# taco.net
KiCad netlist of a schematic drawn in EAGLE
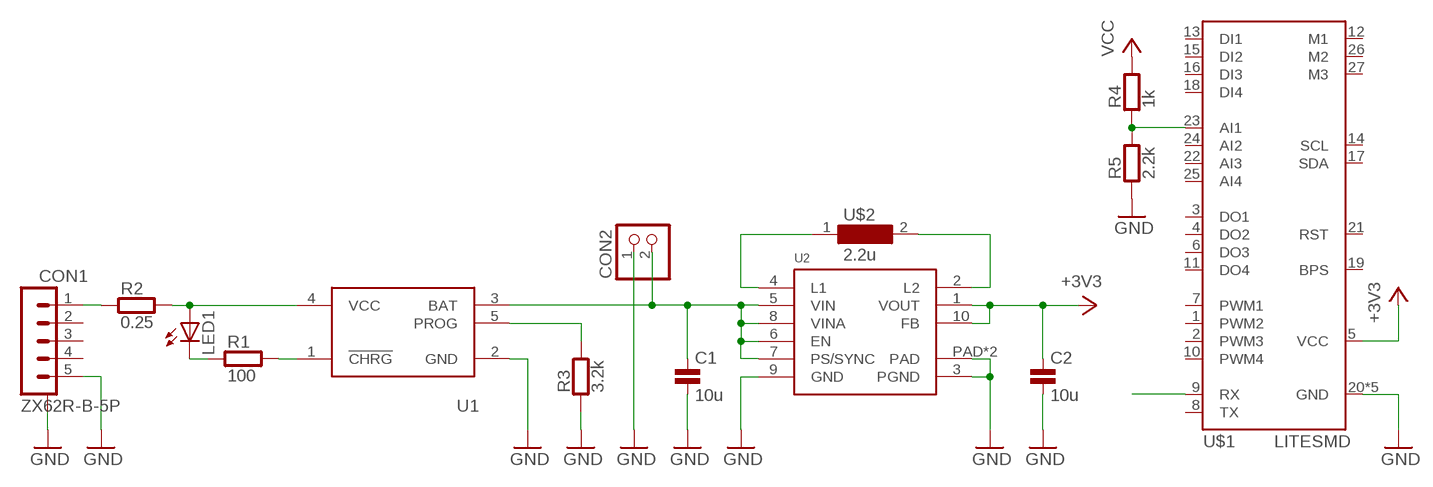
[diagram p0: schematic, sheet 1]

(export (version "E")
  (design (tool "Eeschema 10.0.6"))
  (components
    (comp (ref "C1")
      (value "10u")
      (footprint "eagle-import:0603")
      (libsource (lib "eagle-import") (part "C0603"))
    )
    (comp (ref "C2")
      (value "10u")
      (footprint "eagle-import:0603")
      (libsource (lib "eagle-import") (part "C0603"))
    )
    (comp (ref "CON1")
      (value "ZX62R-B-5P")
      (footprint "eagle-import:MICRO-B")
      (libsource (lib "eagle-import") (part "ZX62R-B-5P"))
    )
    (comp (ref "CON2")
      (value "JST-PH2")
      (footprint "eagle-import:JST-PH2")
      (libsource (lib "eagle-import") (part "JST-PH2"))
    )
    (comp (ref "LED1")
      (value "LEDSML0603")
      (footprint "eagle-import:SML0603")
      (libsource (lib "eagle-import") (part "LEDSML0603"))
    )
    (comp (ref "R1")
      (value "100")
      (footprint "eagle-import:0603")
      (libsource (lib "eagle-import") (part "R0603"))
    )
    (comp (ref "R2")
      (value "0.25")
      (footprint "eagle-import:0603")
      (libsource (lib "eagle-import") (part "R0603"))
    )
    (comp (ref "R3")
      (value "3.2k")
      (footprint "eagle-import:0603")
      (libsource (lib "eagle-import") (part "R0603"))
    )
    (comp (ref "R4")
      (value "1k")
      (footprint "eagle-import:0603")
      (libsource (lib "eagle-import") (part "R0603"))
    )
    (comp (ref "R5")
      (value "2.2k")
      (footprint "eagle-import:0603")
      (libsource (lib "eagle-import") (part "R0603"))
    )
    (comp (ref "U$1")
      (value "LITESMD")
      (footprint "eagle-import:LITE")
      (libsource (lib "eagle-import") (part "LITESMD"))
    )
    (comp (ref "U$2")
      (value "2.2u")
      (footprint "eagle-import:VLF4012ST")
      (libsource (lib "eagle-import") (part "VLF4012ST"))
    )
    (comp (ref "U1")
      (value "LTC4054")
      (footprint "eagle-import:TSOT23-5")
      (libsource (lib "eagle-import") (part "LTC4054"))
    )
    (comp (ref "U2")
      (value "TPS6300XDRCT")
      (footprint "eagle-import:S-PVSON-N10")
      (libsource (lib "eagle-import") (part "TPS6300XDRCT"))
    )
  )
  (nets
    (net (code "1") (name "+3V3") (class "Default")
      (node (ref "C2") (pin "1") (pinfunction "P$1_1") (pintype "passive"))
      (node (ref "U$1") (pin "5") (pinfunction "VCC_5") (pintype "power_in"))
      (node (ref "U2") (pin "1") (pinfunction "VOUT_1") (pintype "output"))
      (node (ref "U2") (pin "10") (pinfunction "FB_10") (pintype "input"))
    )
    (net (code "2") (name "GND") (class "Default")
      (node (ref "C1") (pin "2") (pinfunction "P$2_2") (pintype "passive"))
      (node (ref "C2") (pin "2") (pinfunction "P$2_2") (pintype "passive"))
      (node (ref "CON1") (pin "5") (pinfunction "1.VBUS_5") (pintype "passive"))
      (node (ref "CON1") (pin "CASE@1") (pinfunction "P$1_CASE@1") (pintype "bidirectional"))
      (node (ref "CON1") (pin "CASE@2") (pinfunction "P$1_CASE@2") (pintype "bidirectional"))
      (node (ref "CON1") (pin "CASE@3") (pinfunction "P$1_CASE@3") (pintype "bidirectional"))
      (node (ref "CON1") (pin "CASE@4") (pinfunction "P$1_CASE@4") (pintype "bidirectional"))
      (node (ref "CON2") (pin "1") (pinfunction "1_1") (pintype "passive"))
      (node (ref "R3") (pin "1") (pinfunction "P$1_1") (pintype "passive"))
      (node (ref "R5") (pin "1") (pinfunction "P$1_1") (pintype "passive"))
      (node (ref "U$1") (pin "20") (pinfunction "GND_20") (pintype "power_in"))
      (node (ref "U$1") (pin "28") (pinfunction "GND_28") (pintype "power_in"))
      (node (ref "U$1") (pin "30") (pinfunction "GND_30") (pintype "power_in"))
      (node (ref "U$1") (pin "31") (pinfunction "GND_31") (pintype "power_in"))
      (node (ref "U$1") (pin "32") (pinfunction "GND_32") (pintype "power_in"))
      (node (ref "U1") (pin "2") (pinfunction "GND_2") (pintype "power_in"))
      (node (ref "U2") (pin "3") (pinfunction "PGND_3") (pintype "power_in"))
      (node (ref "U2") (pin "9") (pinfunction "GND_9") (pintype "power_in"))
      (node (ref "U2") (pin "PAD") (pinfunction "PAD_PAD") (pintype "power_in"))
      (node (ref "U2") (pin "PAD@1") (pinfunction "PAD_PAD@1") (pintype "power_in"))
    )
    (net (code "3") (name "Net-(CON1-5.GND)") (class "Default")
      (node (ref "CON1") (pin "1") (pinfunction "5.GND_1") (pintype "passive"))
      (node (ref "R2") (pin "1") (pinfunction "P$1_1") (pintype "passive"))
    )
    (net (code "4") (name "Net-(R1-P$1)") (class "Default")
      (node (ref "LED1") (pin "C") (pinfunction "C_C") (pintype "passive"))
      (node (ref "R1") (pin "1") (pinfunction "P$1_1") (pintype "passive"))
    )
    (net (code "5") (name "Net-(R1-P$2)") (class "Default")
      (node (ref "R1") (pin "2") (pinfunction "P$2_2") (pintype "passive"))
      (node (ref "U1") (pin "1") (pinfunction "~{CHRG}_1") (pintype "output"))
    )
    (net (code "6") (name "Net-(R2-P$2)") (class "Default")
      (node (ref "LED1") (pin "A") (pinfunction "A_A") (pintype "passive"))
      (node (ref "R2") (pin "2") (pinfunction "P$2_2") (pintype "passive"))
      (node (ref "U1") (pin "4") (pinfunction "VCC_4") (pintype "power_in"))
    )
    (net (code "7") (name "Net-(R3-P$2)") (class "Default")
      (node (ref "R3") (pin "2") (pinfunction "P$2_2") (pintype "passive"))
      (node (ref "U1") (pin "5") (pinfunction "PROG_5") (pintype "passive"))
    )
    (net (code "8") (name "Net-(R4-P$1)") (class "Default")
      (node (ref "R4") (pin "1") (pinfunction "P$1_1") (pintype "passive"))
      (node (ref "R5") (pin "2") (pinfunction "P$2_2") (pintype "passive"))
      (node (ref "U$1") (pin "23") (pinfunction "AI1_23") (pintype "input"))
    )
    (net (code "9") (name "Net-(U2-L1)") (class "Default")
      (node (ref "U$2") (pin "1") (pinfunction "1_1") (pintype "passive"))
      (node (ref "U2") (pin "4") (pinfunction "L1_4") (pintype "bidirectional"))
    )
    (net (code "10") (name "Net-(U2-L2)") (class "Default")
      (node (ref "U$2") (pin "2") (pinfunction "2_2") (pintype "passive"))
      (node (ref "U2") (pin "2") (pinfunction "L2_2") (pintype "bidirectional"))
    )
    (net (code "11") (name "VCC") (class "Default")
      (node (ref "C1") (pin "1") (pinfunction "P$1_1") (pintype "passive"))
      (node (ref "CON2") (pin "2") (pinfunction "2_2") (pintype "passive"))
      (node (ref "R4") (pin "2") (pinfunction "P$2_2") (pintype "passive"))
      (node (ref "U1") (pin "3") (pinfunction "BAT_3") (pintype "power_in"))
      (node (ref "U2") (pin "5") (pinfunction "VIN_5") (pintype "power_in"))
      (node (ref "U2") (pin "6") (pinfunction "EN_6") (pintype "input"))
      (node (ref "U2") (pin "7") (pinfunction "PS/SYNC_7") (pintype "input"))
      (node (ref "U2") (pin "8") (pinfunction "VINA_8") (pintype "power_in"))
    )
    (net (code "12") (name "unconnected-(CON1-2.D--Pad4)") (class "Default")
      (node (ref "CON1") (pin "4") (pinfunction "2.D-_4") (pintype "passive"))
    )
    (net (code "13") (name "unconnected-(CON1-3.D+-Pad3)") (class "Default")
      (node (ref "CON1") (pin "3") (pinfunction "3.D+_3") (pintype "passive"))
    )
    (net (code "14") (name "unconnected-(CON1-4.ID-Pad2)") (class "Default")
      (node (ref "CON1") (pin "2") (pinfunction "4.ID_2") (pintype "passive"))
    )
    (net (code "15") (name "unconnected-(U$1-AI2-Pad24)") (class "Default")
      (node (ref "U$1") (pin "24") (pinfunction "AI2_24") (pintype "input"))
    )
    (net (code "16") (name "unconnected-(U$1-AI3-Pad22)") (class "Default")
      (node (ref "U$1") (pin "22") (pinfunction "AI3_22") (pintype "input"))
    )
    (net (code "17") (name "unconnected-(U$1-AI4-Pad25)") (class "Default")
      (node (ref "U$1") (pin "25") (pinfunction "AI4_25") (pintype "input"))
    )
    (net (code "18") (name "unconnected-(U$1-BPS-Pad19)") (class "Default")
      (node (ref "U$1") (pin "19") (pinfunction "BPS_19") (pintype "input"))
    )
    (net (code "19") (name "unconnected-(U$1-DI1-Pad13)") (class "Default")
      (node (ref "U$1") (pin "13") (pinfunction "DI1_13") (pintype "input"))
    )
    (net (code "20") (name "unconnected-(U$1-DI2-Pad15)") (class "Default")
      (node (ref "U$1") (pin "15") (pinfunction "DI2_15") (pintype "input"))
    )
    (net (code "21") (name "unconnected-(U$1-DI3-Pad16)") (class "Default")
      (node (ref "U$1") (pin "16") (pinfunction "DI3_16") (pintype "input"))
    )
    (net (code "22") (name "unconnected-(U$1-DI4-Pad18)") (class "Default")
      (node (ref "U$1") (pin "18") (pinfunction "DI4_18") (pintype "input"))
    )
    (net (code "23") (name "unconnected-(U$1-DO1-Pad3)") (class "Default")
      (node (ref "U$1") (pin "3") (pinfunction "DO1_3") (pintype "output"))
    )
    (net (code "24") (name "unconnected-(U$1-DO2-Pad4)") (class "Default")
      (node (ref "U$1") (pin "4") (pinfunction "DO2_4") (pintype "output"))
    )
    (net (code "25") (name "unconnected-(U$1-DO3-Pad6)") (class "Default")
      (node (ref "U$1") (pin "6") (pinfunction "DO3_6") (pintype "output"))
    )
    (net (code "26") (name "unconnected-(U$1-DO4-Pad11)") (class "Default")
      (node (ref "U$1") (pin "11") (pinfunction "DO4_11") (pintype "output"))
    )
    (net (code "27") (name "unconnected-(U$1-M1-Pad12)") (class "Default")
      (node (ref "U$1") (pin "12") (pinfunction "M1_12") (pintype "input"))
    )
    (net (code "28") (name "unconnected-(U$1-M2-Pad26)") (class "Default")
      (node (ref "U$1") (pin "26") (pinfunction "M2_26") (pintype "input"))
    )
    (net (code "29") (name "unconnected-(U$1-M3-Pad27)") (class "Default")
      (node (ref "U$1") (pin "27") (pinfunction "M3_27") (pintype "input"))
    )
    (net (code "30") (name "unconnected-(U$1-PWM1-Pad7)") (class "Default")
      (node (ref "U$1") (pin "7") (pinfunction "PWM1_7") (pintype "output"))
    )
    (net (code "31") (name "unconnected-(U$1-PWM2-Pad1)") (class "Default")
      (node (ref "U$1") (pin "1") (pinfunction "PWM2_1") (pintype "output"))
    )
    (net (code "32") (name "unconnected-(U$1-PWM3-Pad2)") (class "Default")
      (node (ref "U$1") (pin "2") (pinfunction "PWM3_2") (pintype "output"))
    )
    (net (code "33") (name "unconnected-(U$1-PWM4-Pad10)") (class "Default")
      (node (ref "U$1") (pin "10") (pinfunction "PWM4_10") (pintype "output"))
    )
    (net (code "34") (name "unconnected-(U$1-RST-Pad21)") (class "Default")
      (node (ref "U$1") (pin "21") (pinfunction "RST_21") (pintype "input"))
    )
    (net (code "35") (name "unconnected-(U$1-RX-Pad9)") (class "Default")
      (node (ref "U$1") (pin "9") (pinfunction "RX_9") (pintype "input"))
    )
    (net (code "36") (name "unconnected-(U$1-SCL-Pad14)") (class "Default")
      (node (ref "U$1") (pin "14") (pinfunction "SCL_14") (pintype "bidirectional"))
    )
    (net (code "37") (name "unconnected-(U$1-SDA-Pad17)") (class "Default")
      (node (ref "U$1") (pin "17") (pinfunction "SDA_17") (pintype "bidirectional"))
    )
    (net (code "38") (name "unconnected-(U$1-TX-Pad8)") (class "Default")
      (node (ref "U$1") (pin "8") (pinfunction "TX_8") (pintype "output"))
    )
  )
)
